# AtMega.net
KiCad netlist of a schematic drawn in EAGLE
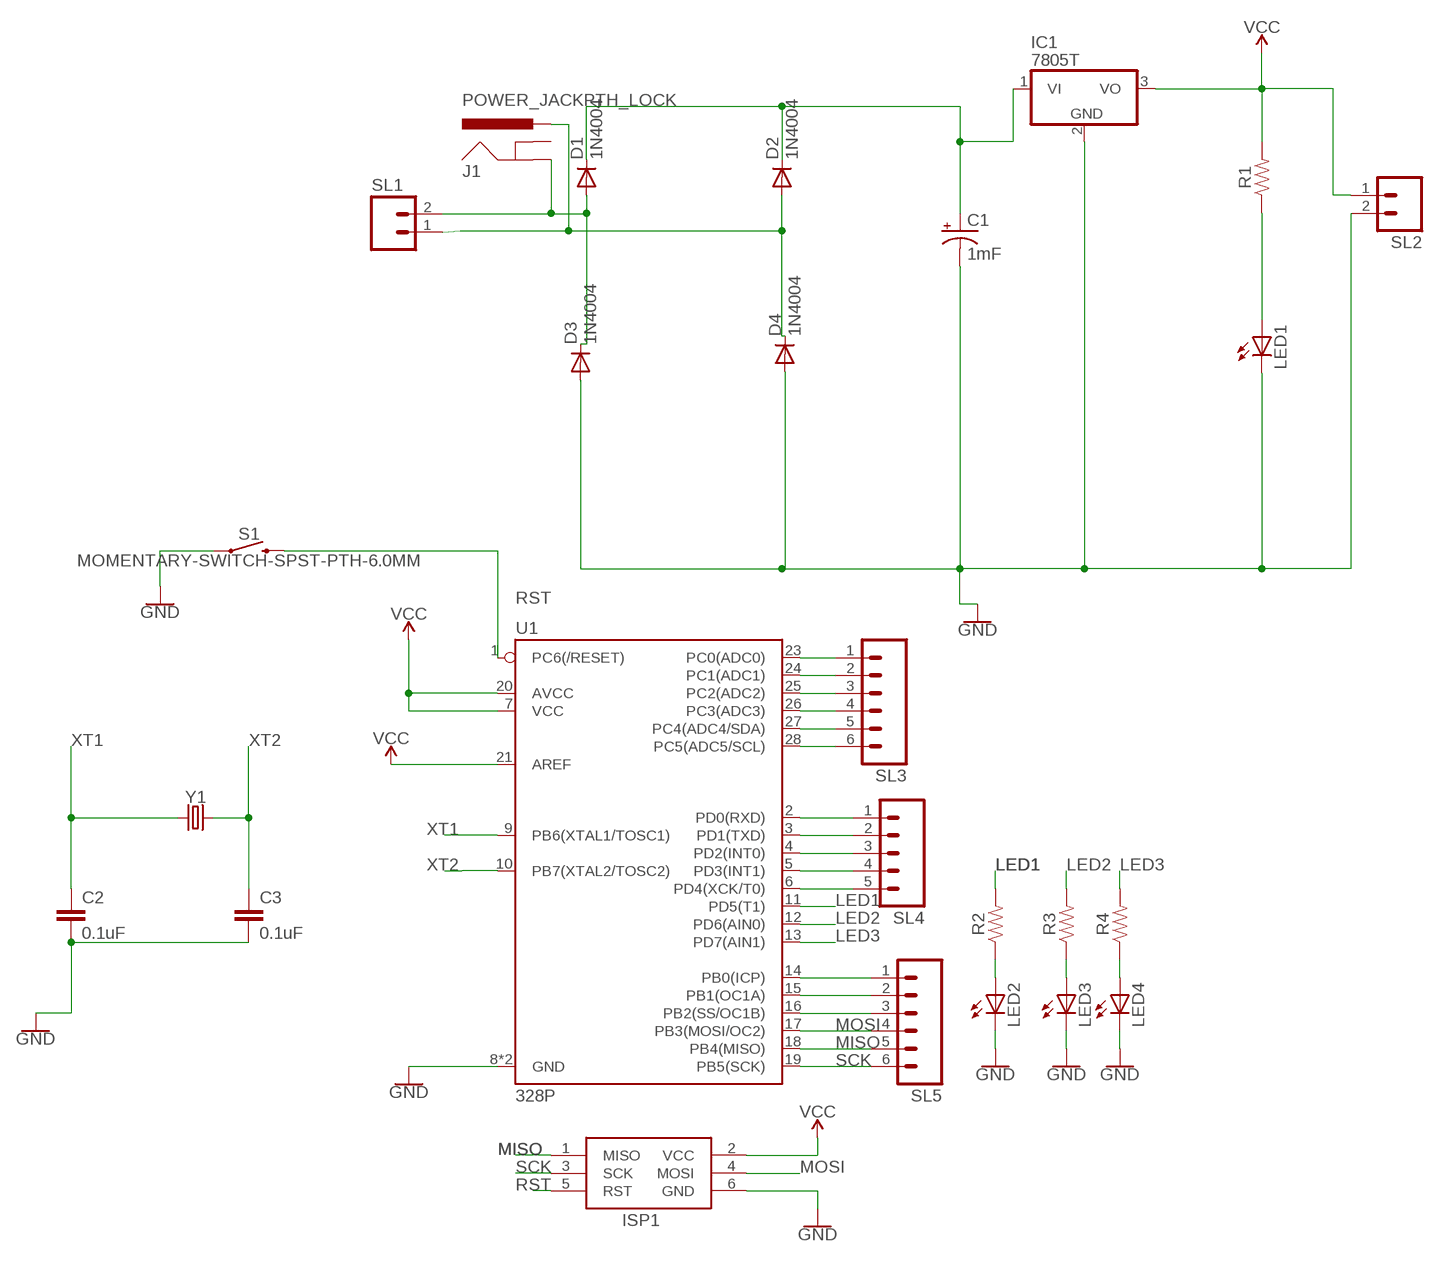
[diagram p0: schematic, sheet 1]

(export (version "E")
  (design (tool "Eeschema 10.0.6"))
  (components
    (comp (ref "C1")
      (value "1mF")
      (footprint "eagle-import:CPOL-RADIAL-5MM-10MM")
      (libsource (lib "eagle-import") (part "1000UF-RADIAL-5MM-25V-20%"))
    )
    (comp (ref "C2")
      (value "0.1uF")
      (footprint "eagle-import:CAP-PTH-SMALL-KIT")
      (libsource (lib "eagle-import") (part "0.1UF-KIT-EZ-50V-20%"))
    )
    (comp (ref "C3")
      (value "0.1uF")
      (footprint "eagle-import:CAP-PTH-SMALL-KIT")
      (libsource (lib "eagle-import") (part "0.1UF-KIT-EZ-50V-20%"))
    )
    (comp (ref "D1")
      (value "1N4004")
      (footprint "eagle-import:DO41-10")
      (libsource (lib "eagle-import") (part "1N4004"))
    )
    (comp (ref "D2")
      (value "1N4004")
      (footprint "eagle-import:DO41-10")
      (libsource (lib "eagle-import") (part "1N4004"))
    )
    (comp (ref "D3")
      (value "1N4004")
      (footprint "eagle-import:DO41-10")
      (libsource (lib "eagle-import") (part "1N4004"))
    )
    (comp (ref "D4")
      (value "1N4004")
      (footprint "eagle-import:DO41-10")
      (libsource (lib "eagle-import") (part "1N4004"))
    )
    (comp (ref "IC1")
      (value "7805T")
      (footprint "eagle-import:TO220H")
      (libsource (lib "eagle-import") (part "78T05"))
    )
    (comp (ref "ISP1")
      (value "AVRISP-6")
      (footprint "eagle-import:AVRISP")
      (libsource (lib "eagle-import") (part "AVRISP-6"))
    )
    (comp (ref "J1")
      (value "POWER_JACKPTH_LOCK")
      (footprint "eagle-import:POWER_JACK_PTH_LOCK")
      (libsource (lib "eagle-import") (part "POWER_JACKPTH_LOCK"))
    )
    (comp (ref "LED1")
      (value "LED5MM")
      (footprint "eagle-import:LED5MM")
      (libsource (lib "eagle-import") (part "LED5MM"))
    )
    (comp (ref "LED2")
      (value "LED3MM")
      (footprint "eagle-import:LED3MM")
      (libsource (lib "eagle-import") (part "LED3MM"))
    )
    (comp (ref "LED3")
      (value "LED3MM")
      (footprint "eagle-import:LED3MM")
      (libsource (lib "eagle-import") (part "LED3MM"))
    )
    (comp (ref "LED4")
      (value "LED3MM")
      (footprint "eagle-import:LED3MM")
      (libsource (lib "eagle-import") (part "LED3MM"))
    )
    (comp (ref "R1")
      (value "RESISTORAXIAL-0.3")
      (footprint "eagle-import:AXIAL-0.3")
      (libsource (lib "eagle-import") (part "RESISTORAXIAL-0.3"))
    )
    (comp (ref "R2")
      (value "RESISTORAXIAL-0.3")
      (footprint "eagle-import:AXIAL-0.3")
      (libsource (lib "eagle-import") (part "RESISTORAXIAL-0.3"))
    )
    (comp (ref "R3")
      (value "RESISTORAXIAL-0.3")
      (footprint "eagle-import:AXIAL-0.3")
      (libsource (lib "eagle-import") (part "RESISTORAXIAL-0.3"))
    )
    (comp (ref "R4")
      (value "RESISTORAXIAL-0.3")
      (footprint "eagle-import:AXIAL-0.3")
      (libsource (lib "eagle-import") (part "RESISTORAXIAL-0.3"))
    )
    (comp (ref "S1")
      (value "MOMENTARY-SWITCH-SPST-PTH-6.0MM")
      (footprint "eagle-import:TACTILE_SWITCH_PTH_6.0MM")
      (libsource (lib "eagle-import") (part "MOMENTARY-SWITCH-SPST-PTH-6.0MM"))
    )
    (comp (ref "SL1")
      (value "M02")
      (footprint "eagle-import:02P")
      (libsource (lib "eagle-import") (part "M02"))
    )
    (comp (ref "SL2")
      (value "M02")
      (footprint "eagle-import:02P")
      (libsource (lib "eagle-import") (part "M02"))
    )
    (comp (ref "SL3")
      (value "M06")
      (footprint "eagle-import:06P")
      (libsource (lib "eagle-import") (part "M06"))
    )
    (comp (ref "SL4")
      (value "M05")
      (footprint "eagle-import:05P")
      (libsource (lib "eagle-import") (part "M05"))
    )
    (comp (ref "SL5")
      (value "M06")
      (footprint "eagle-import:06P")
      (libsource (lib "eagle-import") (part "M06"))
    )
    (comp (ref "U1")
      (value "328P")
      (footprint "eagle-import:DIP28")
      (libsource (lib "eagle-import") (part "ATMEGA328P_PDIP"))
    )
    (comp (ref "Y1")
      (value "CRYSTALPTH-HC49US")
      (footprint "eagle-import:HC49US")
      (libsource (lib "eagle-import") (part "CRYSTALPTH-HC49US"))
    )
  )
  (nets
    (net (code "1") (name "/LED1") (class "Default")
      (node (ref "R2") (pin "P$2") (pinfunction "2_P$2") (pintype "passive"))
      (node (ref "U1") (pin "11") (pinfunction "PD5(T1)_11") (pintype "bidirectional"))
    )
    (net (code "2") (name "/LED2") (class "Default")
      (node (ref "R3") (pin "P$2") (pinfunction "2_P$2") (pintype "passive"))
      (node (ref "U1") (pin "12") (pinfunction "PD6(AIN0)_12") (pintype "bidirectional"))
    )
    (net (code "3") (name "/LED3") (class "Default")
      (node (ref "R4") (pin "P$2") (pinfunction "2_P$2") (pintype "passive"))
      (node (ref "U1") (pin "13") (pinfunction "PD7(AIN1)_13") (pintype "bidirectional"))
    )
    (net (code "4") (name "/MISO") (class "Default")
      (node (ref "ISP1") (pin "1") (pinfunction "MISO_1") (pintype "input"))
      (node (ref "SL5") (pin "5") (pinfunction "5_5") (pintype "passive"))
      (node (ref "U1") (pin "18") (pinfunction "PB4(MISO)_18") (pintype "bidirectional"))
    )
    (net (code "5") (name "/MOSI") (class "Default")
      (node (ref "ISP1") (pin "4") (pinfunction "MOSI_4") (pintype "output"))
      (node (ref "SL5") (pin "4") (pinfunction "4_4") (pintype "passive"))
      (node (ref "U1") (pin "17") (pinfunction "PB3(MOSI/OC2)_17") (pintype "bidirectional"))
    )
    (net (code "6") (name "/RST") (class "Default")
      (node (ref "ISP1") (pin "5") (pinfunction "RST_5") (pintype "output"))
      (node (ref "S1") (pin "3") (pinfunction "2_3") (pintype "passive"))
      (node (ref "U1") (pin "1") (pinfunction "PC6(/RESET)_1") (pintype "bidirectional"))
    )
    (net (code "7") (name "/SCK") (class "Default")
      (node (ref "ISP1") (pin "3") (pinfunction "SCK_3") (pintype "output"))
      (node (ref "SL5") (pin "6") (pinfunction "6_6") (pintype "passive"))
      (node (ref "U1") (pin "19") (pinfunction "PB5(SCK)_19") (pintype "bidirectional"))
    )
    (net (code "8") (name "/XT1") (class "Default")
      (node (ref "C2") (pin "1") (pinfunction "1_1") (pintype "passive"))
      (node (ref "U1") (pin "9") (pinfunction "PB6(XTAL1/TOSC1)_9") (pintype "bidirectional"))
      (node (ref "Y1") (pin "1") (pinfunction "1_1") (pintype "passive"))
    )
    (net (code "9") (name "/XT2") (class "Default")
      (node (ref "C3") (pin "1") (pinfunction "1_1") (pintype "passive"))
      (node (ref "U1") (pin "10") (pinfunction "PB7(XTAL2/TOSC2)_10") (pintype "bidirectional"))
      (node (ref "Y1") (pin "2") (pinfunction "2_2") (pintype "passive"))
    )
    (net (code "10") (name "GND") (class "Default")
      (node (ref "C1") (pin "-") (pinfunction "-_-") (pintype "passive"))
      (node (ref "C2") (pin "2") (pinfunction "2_2") (pintype "passive"))
      (node (ref "C3") (pin "2") (pinfunction "2_2") (pintype "passive"))
      (node (ref "D3") (pin "A") (pinfunction "A_A") (pintype "passive"))
      (node (ref "IC1") (pin "2") (pinfunction "GND_2") (pintype "passive"))
      (node (ref "ISP1") (pin "6") (pinfunction "GND_6") (pintype "power_in"))
      (node (ref "LED1") (pin "K") (pinfunction "C_K") (pintype "passive"))
      (node (ref "LED2") (pin "K") (pinfunction "C_K") (pintype "passive"))
      (node (ref "LED3") (pin "K") (pinfunction "C_K") (pintype "passive"))
      (node (ref "LED4") (pin "K") (pinfunction "C_K") (pintype "passive"))
      (node (ref "S1") (pin "1") (pinfunction "1_1") (pintype "passive"))
      (node (ref "SL2") (pin "2") (pinfunction "2_2") (pintype "passive"))
      (node (ref "U1") (pin "22") (pinfunction "GND_22") (pintype "bidirectional"))
      (node (ref "U1") (pin "8") (pinfunction "GND_8") (pintype "bidirectional"))
    )
    (net (code "11") (name "Net-(D1-PadA)") (class "Default")
      (node (ref "D1") (pin "A") (pinfunction "A_A") (pintype "passive"))
      (node (ref "D3") (pin "C") (pinfunction "C_C") (pintype "passive"))
      (node (ref "SL1") (pin "2") (pinfunction "2_2") (pintype "passive"))
    )
    (net (code "12") (name "Net-(D2-PadA)") (class "Default")
      (node (ref "D2") (pin "A") (pinfunction "A_A") (pintype "passive"))
      (node (ref "D4") (pin "C") (pinfunction "C_C") (pintype "passive"))
      (node (ref "J1") (pin "PWR") (pinfunction "PWR_PWR") (pintype "bidirectional"))
      (node (ref "SL1") (pin "1") (pinfunction "1_1") (pintype "passive"))
    )
    (net (code "13") (name "Net-(IC1-VI)") (class "Default")
      (node (ref "C1") (pin "+") (pinfunction "+_+") (pintype "passive"))
      (node (ref "D1") (pin "C") (pinfunction "C_C") (pintype "passive"))
      (node (ref "D2") (pin "C") (pinfunction "C_C") (pintype "passive"))
      (node (ref "IC1") (pin "1") (pinfunction "VI_1") (pintype "input"))
    )
    (net (code "14") (name "Net-(R1-1)") (class "Default")
      (node (ref "LED1") (pin "A") (pinfunction "A_A") (pintype "passive"))
      (node (ref "R1") (pin "P$1") (pinfunction "1_P$1") (pintype "passive"))
    )
    (net (code "15") (name "Net-(R2-1)") (class "Default")
      (node (ref "LED2") (pin "A") (pinfunction "A_A") (pintype "passive"))
      (node (ref "R2") (pin "P$1") (pinfunction "1_P$1") (pintype "passive"))
    )
    (net (code "16") (name "Net-(R3-1)") (class "Default")
      (node (ref "LED3") (pin "A") (pinfunction "A_A") (pintype "passive"))
      (node (ref "R3") (pin "P$1") (pinfunction "1_P$1") (pintype "passive"))
    )
    (net (code "17") (name "Net-(R4-1)") (class "Default")
      (node (ref "LED4") (pin "A") (pinfunction "A_A") (pintype "passive"))
      (node (ref "R4") (pin "P$1") (pinfunction "1_P$1") (pintype "passive"))
    )
    (net (code "18") (name "Net-(U1-PB0(ICP))") (class "Default")
      (node (ref "SL5") (pin "1") (pinfunction "1_1") (pintype "passive"))
      (node (ref "U1") (pin "14") (pinfunction "PB0(ICP)_14") (pintype "bidirectional"))
    )
    (net (code "19") (name "Net-(U1-PB1(OC1A))") (class "Default")
      (node (ref "SL5") (pin "2") (pinfunction "2_2") (pintype "passive"))
      (node (ref "U1") (pin "15") (pinfunction "PB1(OC1A)_15") (pintype "bidirectional"))
    )
    (net (code "20") (name "Net-(U1-PB2(SS{slash}OC1B))") (class "Default")
      (node (ref "SL5") (pin "3") (pinfunction "3_3") (pintype "passive"))
      (node (ref "U1") (pin "16") (pinfunction "PB2(SS/OC1B)_16") (pintype "bidirectional"))
    )
    (net (code "21") (name "Net-(U1-PC0(ADC0))") (class "Default")
      (node (ref "SL3") (pin "1") (pinfunction "1_1") (pintype "passive"))
      (node (ref "U1") (pin "23") (pinfunction "PC0(ADC0)_23") (pintype "bidirectional"))
    )
    (net (code "22") (name "Net-(U1-PC1(ADC1))") (class "Default")
      (node (ref "SL3") (pin "2") (pinfunction "2_2") (pintype "passive"))
      (node (ref "U1") (pin "24") (pinfunction "PC1(ADC1)_24") (pintype "bidirectional"))
    )
    (net (code "23") (name "Net-(U1-PC2(ADC2))") (class "Default")
      (node (ref "SL3") (pin "3") (pinfunction "3_3") (pintype "passive"))
      (node (ref "U1") (pin "25") (pinfunction "PC2(ADC2)_25") (pintype "bidirectional"))
    )
    (net (code "24") (name "Net-(U1-PC3(ADC3))") (class "Default")
      (node (ref "SL3") (pin "4") (pinfunction "4_4") (pintype "passive"))
      (node (ref "U1") (pin "26") (pinfunction "PC3(ADC3)_26") (pintype "bidirectional"))
    )
    (net (code "25") (name "Net-(U1-PC4(ADC4{slash}SDA))") (class "Default")
      (node (ref "SL3") (pin "5") (pinfunction "5_5") (pintype "passive"))
      (node (ref "U1") (pin "27") (pinfunction "PC4(ADC4/SDA)_27") (pintype "bidirectional"))
    )
    (net (code "26") (name "Net-(U1-PC5(ADC5{slash}SCL))") (class "Default")
      (node (ref "SL3") (pin "6") (pinfunction "6_6") (pintype "passive"))
      (node (ref "U1") (pin "28") (pinfunction "PC5(ADC5/SCL)_28") (pintype "bidirectional"))
    )
    (net (code "27") (name "Net-(U1-PD0(RXD))") (class "Default")
      (node (ref "SL4") (pin "1") (pinfunction "1_1") (pintype "passive"))
      (node (ref "U1") (pin "2") (pinfunction "PD0(RXD)_2") (pintype "bidirectional"))
    )
    (net (code "28") (name "Net-(U1-PD1(TXD))") (class "Default")
      (node (ref "SL4") (pin "2") (pinfunction "2_2") (pintype "passive"))
      (node (ref "U1") (pin "3") (pinfunction "PD1(TXD)_3") (pintype "bidirectional"))
    )
    (net (code "29") (name "Net-(U1-PD2(INT0))") (class "Default")
      (node (ref "SL4") (pin "3") (pinfunction "3_3") (pintype "passive"))
      (node (ref "U1") (pin "4") (pinfunction "PD2(INT0)_4") (pintype "bidirectional"))
    )
    (net (code "30") (name "Net-(U1-PD3(INT1))") (class "Default")
      (node (ref "SL4") (pin "4") (pinfunction "4_4") (pintype "passive"))
      (node (ref "U1") (pin "5") (pinfunction "PD3(INT1)_5") (pintype "bidirectional"))
    )
    (net (code "31") (name "Net-(U1-PD4(XCK{slash}T0))") (class "Default")
      (node (ref "SL4") (pin "5") (pinfunction "5_5") (pintype "passive"))
      (node (ref "U1") (pin "6") (pinfunction "PD4(XCK/T0)_6") (pintype "bidirectional"))
    )
    (net (code "32") (name "VCC") (class "Default")
      (node (ref "IC1") (pin "3") (pinfunction "VO_3") (pintype "passive"))
      (node (ref "ISP1") (pin "2") (pinfunction "VCC_2") (pintype "power_in"))
      (node (ref "R1") (pin "P$2") (pinfunction "2_P$2") (pintype "passive"))
      (node (ref "SL2") (pin "1") (pinfunction "1_1") (pintype "passive"))
      (node (ref "U1") (pin "20") (pinfunction "AVCC_20") (pintype "bidirectional"))
      (node (ref "U1") (pin "21") (pinfunction "AREF_21") (pintype "bidirectional"))
      (node (ref "U1") (pin "7") (pinfunction "VCC_7") (pintype "bidirectional"))
    )
    (net (code "33") (name "unconnected-(D4-PadA)") (class "Default")
      (node (ref "D4") (pin "A") (pinfunction "A_A") (pintype "passive"))
    )
    (net (code "34") (name "unconnected-(J1-PadGND)") (class "Default")
      (node (ref "J1") (pin "GND") (pinfunction "GND_GND") (pintype "bidirectional"))
    )
    (net (code "35") (name "unconnected-(J1-PadGNDBREAK)") (class "Default")
      (node (ref "J1") (pin "GNDBREAK") (pinfunction "GNDBREAK_GNDBREAK") (pintype "bidirectional"))
    )
  )
)
